# ETH_IFC.net
KiCad netlist of a schematic drawn in Altium Designer
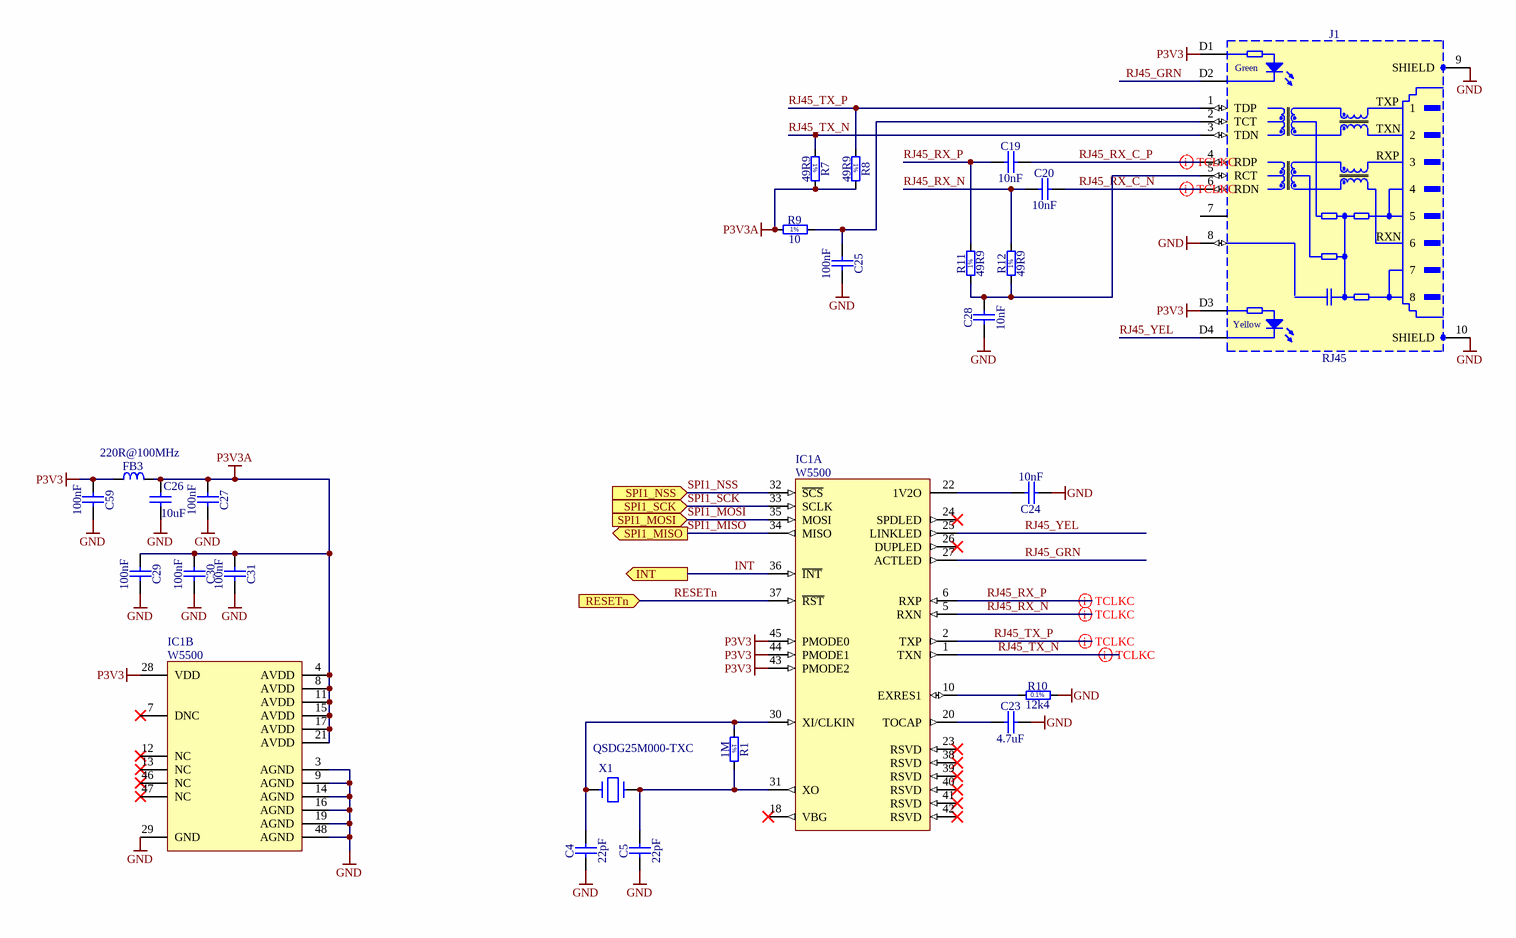
[diagram p0: ETH_IFC.SchDoc]

(export (version "E")
  (design (tool "Eeschema 10.0.6"))
  (components
    (comp (ref "C4")
      (value "22pF")
      (footprint "CAPC1005X55N")
      (description "Non-polarised capacitor")
      (fields
        (field (name "PART NUMBER") "CC0402_22PF_50V_5%_NP0")
        (field (name "VOLTAGE") "50V")
        (field (name "AUTHOR") "CERN DEM JLC")
      )
      (libsource (lib "Capacitors") (part "Capacitor - non polarized"))
    )
    (comp (ref "C5")
      (value "22pF")
      (footprint "CAPC1005X55N")
      (description "Non-polarised capacitor")
      (fields
        (field (name "PART NUMBER") "CC0402_22PF_50V_5%_NP0")
        (field (name "VOLTAGE") "50V")
        (field (name "AUTHOR") "CERN DEM JLC")
      )
      (libsource (lib "Capacitors") (part "Capacitor - non polarized"))
    )
    (comp (ref "C19")
      (value "10nF")
      (footprint "CAPC1608X87N")
      (description "Non-polarised capacitor")
      (fields
        (field (name "PART NUMBER") "CC0603_10NF_50V_5%_C0G")
        (field (name "VOLTAGE") "50V")
        (field (name "AUTHOR") "CERN DEM JLC")
      )
      (libsource (lib "Capacitors") (part "Capacitor - non polarized"))
    )
    (comp (ref "C20")
      (value "10nF")
      (footprint "CAPC1608X87N")
      (description "Non-polarised capacitor")
      (fields
        (field (name "PART NUMBER") "CC0603_10NF_50V_5%_C0G")
        (field (name "VOLTAGE") "50V")
        (field (name "AUTHOR") "CERN DEM JLC")
      )
      (libsource (lib "Capacitors") (part "Capacitor - non polarized"))
    )
    (comp (ref "C23")
      (value "4.7uF")
      (footprint "CAPC1709X95N")
      (description "Non-polarised capacitor")
      (fields
        (field (name "PART NUMBER") "CC0603_4.7UF_16V_10%_X5R")
        (field (name "VOLTAGE") "16V")
        (field (name "AUTHOR") "CERN DEM JLC")
      )
      (libsource (lib "Capacitors") (part "Capacitor - non polarized"))
    )
    (comp (ref "C24")
      (value "10nF")
      (footprint "CAPC1608X87N")
      (description "Non-polarised capacitor")
      (fields
        (field (name "PART NUMBER") "CC0603_10NF_50V_5%_C0G")
        (field (name "VOLTAGE") "50V")
        (field (name "AUTHOR") "CERN DEM JLC")
      )
      (libsource (lib "Capacitors") (part "Capacitor - non polarized"))
    )
    (comp (ref "C25")
      (value "100nF")
      (footprint "CAPC1005X55N")
      (description "Non-polarised capacitor")
      (fields
        (field (name "PART NUMBER") "CC0402_100NF_16V_10%_X7R")
        (field (name "VOLTAGE") "16V")
        (field (name "AUTHOR") "CERN DEM JLC")
      )
      (libsource (lib "Capacitors") (part "Capacitor - non polarized"))
    )
    (comp (ref "C26")
      (value "10uF")
      (footprint "CAPC2012X135N")
      (description "Non-polarised capacitor")
      (fields
        (field (name "PART NUMBER") "CC0805_10UF_10V_10%_X7R")
        (field (name "VOLTAGE") "10V")
        (field (name "AUTHOR") "CERN DEM JLC")
      )
      (libsource (lib "Capacitors") (part "Capacitor - non polarized"))
    )
    (comp (ref "C27")
      (value "100nF")
      (footprint "CAPC1005X55N")
      (description "Non-polarised capacitor")
      (fields
        (field (name "PART NUMBER") "CC0402_100NF_16V_10%_X7R")
        (field (name "VOLTAGE") "16V")
        (field (name "AUTHOR") "CERN DEM JLC")
      )
      (libsource (lib "Capacitors") (part "Capacitor - non polarized"))
    )
    (comp (ref "C28")
      (value "10nF")
      (footprint "CAPC1608X87N")
      (description "Non-polarised capacitor")
      (fields
        (field (name "PART NUMBER") "CC0603_10NF_50V_5%_C0G")
        (field (name "VOLTAGE") "50V")
        (field (name "AUTHOR") "CERN DEM JLC")
      )
      (libsource (lib "Capacitors") (part "Capacitor - non polarized"))
    )
    (comp (ref "C29")
      (value "100nF")
      (footprint "CAPC1005X55N")
      (description "Non-polarised capacitor")
      (fields
        (field (name "PART NUMBER") "CC0402_100NF_16V_10%_X7R")
        (field (name "VOLTAGE") "16V")
        (field (name "AUTHOR") "CERN DEM JLC")
      )
      (libsource (lib "Capacitors") (part "Capacitor - non polarized"))
    )
    (comp (ref "C30")
      (value "100nF")
      (footprint "CAPC1005X55N")
      (description "Non-polarised capacitor")
      (fields
        (field (name "PART NUMBER") "CC0402_100NF_16V_10%_X7R")
        (field (name "VOLTAGE") "16V")
        (field (name "AUTHOR") "CERN DEM JLC")
      )
      (libsource (lib "Capacitors") (part "Capacitor - non polarized"))
    )
    (comp (ref "C31")
      (value "100nF")
      (footprint "CAPC1005X55N")
      (description "Non-polarised capacitor")
      (fields
        (field (name "PART NUMBER") "CC0402_100NF_16V_10%_X7R")
        (field (name "VOLTAGE") "16V")
        (field (name "AUTHOR") "CERN DEM JLC")
      )
      (libsource (lib "Capacitors") (part "Capacitor - non polarized"))
    )
    (comp (ref "C59")
      (value "100nF")
      (footprint "CAPC1005X55N")
      (description "Non-polarised capacitor")
      (fields
        (field (name "PART NUMBER") "CC0402_100NF_16V_10%_X7R")
        (field (name "VOLTAGE") "16V")
        (field (name "AUTHOR") "CERN DEM JLC")
      )
      (libsource (lib "Capacitors") (part "Capacitor - non polarized"))
    )
    (comp (ref "FB3")
      (value "220R@100MHz")
      (footprint "INDC2012X105N")
      (description "Inductor")
      (fields
        (field (name "PART NUMBER") "IND0805_MURATA_BLM21PG221SN1D")
        (field (name "POWER") "2A")
        (field (name "AUTHOR") "CERN DEM JLC")
      )
      (libsource (lib "Inductors & Transformers") (part "Inductor"))
    )
    (comp (ref "IC1")
      (value "W5500")
      (footprint "QFP50P900X900X160-48N")
      (description "iEthernet W5500 TCP/IP Performance and High Speed SPI Ethernet Controller")
      (fields (field (name "MANUFACTURER") "WIZNET") (field (name "AUTHOR") "CERN DEM MR"))
      (libsource (lib "ICs And Semiconductors") (part "W5500"))
    )
    (comp (ref "J1")
      (value "RJ45")
      (footprint "TYCO_5-6605308-1")
      (fields
        (field (name "PART NUMBER") "TYCO_5-6605308-1")
        (field (name "MANUFACTURER") "TYCO ELECTRONICS")
        (field (name "MANUFACTURER PART NUMBER") "5-6605308-1")
        (field (name "AUTHOR") "CERN DEM JLC")
      )
      (libsource (lib "Connectors") (part "TYCO_5-6605308-1"))
    )
    (comp (ref "R1")
      (value "1M")
      (footprint "RESC1005X40N")
      (description "Resistor - 1%")
      (fields
        (field (name "PART NUMBER") "R0402_1M_1%_0.0625W_100PPM")
        (field (name "POWER") "0.0625W")
        (field (name "AUTHOR") "CERN DEM JLC")
      )
      (libsource (lib "Resistors") (part "Resistor - 1%"))
    )
    (comp (ref "R7")
      (value "49R9")
      (footprint "RESC1005X40N")
      (description "Resistor - 1%")
      (fields
        (field (name "PART NUMBER") "R0402_49R9_1%_0.0625W_100PPM")
        (field (name "POWER") "0.0625W")
        (field (name "AUTHOR") "CERN DEM JLC")
      )
      (libsource (lib "Resistors") (part "Resistor - 1%"))
    )
    (comp (ref "R8")
      (value "49R9")
      (footprint "RESC1005X40N")
      (description "Resistor - 1%")
      (fields
        (field (name "PART NUMBER") "R0402_49R9_1%_0.0625W_100PPM")
        (field (name "POWER") "0.0625W")
        (field (name "AUTHOR") "CERN DEM JLC")
      )
      (libsource (lib "Resistors") (part "Resistor - 1%"))
    )
    (comp (ref "R9")
      (value "10")
      (footprint "RESC1005X40N")
      (description "Resistor - 1%")
      (fields
        (field (name "PART NUMBER") "R0402_10R_1%_0.0625W_200PPM")
        (field (name "POWER") "0.0625W")
        (field (name "AUTHOR") "CERN DEM JLC")
      )
      (libsource (lib "Resistors") (part "Resistor - 1%"))
    )
    (comp (ref "R10")
      (value "12k4")
      (footprint "RESC1608X55N")
      (description "Resistor - 0.1%")
      (fields
        (field (name "PART NUMBER") "R0603_12K4_0.1%_0.063W_10PPM")
        (field (name "POWER") "0.063W")
        (field (name "AUTHOR") "CERN DEM JLC")
      )
      (libsource (lib "Resistors") (part "Resistor - 0.1%"))
    )
    (comp (ref "R11")
      (value "49R9")
      (footprint "RESC1005X40N")
      (description "Resistor - 1%")
      (fields
        (field (name "PART NUMBER") "R0402_49R9_1%_0.0625W_100PPM")
        (field (name "POWER") "0.0625W")
        (field (name "AUTHOR") "CERN DEM JLC")
      )
      (libsource (lib "Resistors") (part "Resistor - 1%"))
    )
    (comp (ref "R12")
      (value "49R9")
      (footprint "RESC1005X40N")
      (description "Resistor - 1%")
      (fields
        (field (name "PART NUMBER") "R0402_49R9_1%_0.0625W_100PPM")
        (field (name "POWER") "0.0625W")
        (field (name "AUTHOR") "CERN DEM JLC")
      )
      (libsource (lib "Resistors") (part "Resistor - 1%"))
    )
    (comp (ref "X1")
      (value "QSDG25M000-TXC")
      (footprint "XTAL_5.0*3.2")
      (description "miniature crystal oscillator (Maritex)")
      (libsource (lib "LIBRARY_SCH") (part "X_CRYSTAL_SMD_5.0*3.2"))
    )
  )
  (nets
    (net (code "1") (name "/INT") (class "Default")
      (node (ref "IC1") (pin "36") (pinfunction "~{INT}_36") (pintype "input"))
    )
    (net (code "2") (name "/RESETn") (class "Default")
      (node (ref "IC1") (pin "37") (pinfunction "~{RST}_37") (pintype "input"))
    )
    (net (code "3") (name "/RJ45_GRN") (class "Default")
      (node (ref "IC1") (pin "27") (pinfunction "ACTLED_27") (pintype "output"))
      (node (ref "J1") (pin "D2") (pinfunction "D2_D2") (pintype "passive"))
    )
    (net (code "4") (name "/RJ45_RX_C_N") (class "Default")
      (node (ref "C20") (pin "2") (pinfunction "2_2") (pintype "passive"))
      (node (ref "J1") (pin "6") (pinfunction "RDN_6") (pintype "bidirectional"))
    )
    (net (code "5") (name "/RJ45_RX_C_P") (class "Default")
      (node (ref "C19") (pin "2") (pinfunction "2_2") (pintype "passive"))
      (node (ref "J1") (pin "4") (pinfunction "RDP_4") (pintype "bidirectional"))
    )
    (net (code "6") (name "/RJ45_RX_N") (class "Default")
      (node (ref "C20") (pin "1") (pinfunction "1_1") (pintype "passive"))
      (node (ref "IC1") (pin "5") (pinfunction "RXN_5") (pintype "input"))
      (node (ref "R12") (pin "2") (pinfunction "2_2") (pintype "passive"))
    )
    (net (code "7") (name "/RJ45_RX_P") (class "Default")
      (node (ref "C19") (pin "1") (pinfunction "1_1") (pintype "passive"))
      (node (ref "IC1") (pin "6") (pinfunction "RXP_6") (pintype "input"))
      (node (ref "R11") (pin "2") (pinfunction "2_2") (pintype "passive"))
    )
    (net (code "8") (name "/RJ45_TX_N") (class "Default")
      (node (ref "IC1") (pin "1") (pinfunction "TXN_1") (pintype "output"))
      (node (ref "J1") (pin "3") (pinfunction "TDN_3") (pintype "bidirectional"))
      (node (ref "R7") (pin "1") (pinfunction "1_1") (pintype "passive"))
    )
    (net (code "9") (name "/RJ45_TX_P") (class "Default")
      (node (ref "IC1") (pin "2") (pinfunction "TXP_2") (pintype "output"))
      (node (ref "J1") (pin "1") (pinfunction "TDP_1") (pintype "bidirectional"))
      (node (ref "R8") (pin "1") (pinfunction "1_1") (pintype "passive"))
    )
    (net (code "10") (name "/RJ45_YEL") (class "Default")
      (node (ref "IC1") (pin "25") (pinfunction "LINKLED_25") (pintype "output"))
      (node (ref "J1") (pin "D4") (pinfunction "D4_D4") (pintype "passive"))
    )
    (net (code "11") (name "/SPI1_MISO") (class "Default")
      (node (ref "IC1") (pin "34") (pinfunction "MISO_34") (pintype "output"))
    )
    (net (code "12") (name "/SPI1_MOSI") (class "Default")
      (node (ref "IC1") (pin "35") (pinfunction "MOSI_35") (pintype "input"))
    )
    (net (code "13") (name "/SPI1_NSS") (class "Default")
      (node (ref "IC1") (pin "32") (pinfunction "~{SCS}_32") (pintype "input"))
    )
    (net (code "14") (name "/SPI1_SCK") (class "Default")
      (node (ref "IC1") (pin "33") (pinfunction "SCLK_33") (pintype "input"))
    )
    (net (code "15") (name "GND") (class "Default")
      (node (ref "C23") (pin "2") (pinfunction "2_2") (pintype "passive"))
      (node (ref "C24") (pin "1") (pinfunction "1_1") (pintype "passive"))
      (node (ref "C25") (pin "2") (pinfunction "2_2") (pintype "passive"))
      (node (ref "C26") (pin "2") (pinfunction "2_2") (pintype "passive"))
      (node (ref "C27") (pin "2") (pinfunction "2_2") (pintype "passive"))
      (node (ref "C28") (pin "1") (pinfunction "1_1") (pintype "passive"))
      (node (ref "C29") (pin "2") (pinfunction "2_2") (pintype "passive"))
      (node (ref "C30") (pin "2") (pinfunction "2_2") (pintype "passive"))
      (node (ref "C31") (pin "2") (pinfunction "2_2") (pintype "passive"))
      (node (ref "C4") (pin "1") (pinfunction "1_1") (pintype "passive"))
      (node (ref "C5") (pin "1") (pinfunction "1_1") (pintype "passive"))
      (node (ref "C59") (pin "2") (pinfunction "2_2") (pintype "passive"))
      (node (ref "IC1") (pin "14") (pinfunction "AGND_14") (pintype "power_in"))
      (node (ref "IC1") (pin "16") (pinfunction "AGND_16") (pintype "power_in"))
      (node (ref "IC1") (pin "19") (pinfunction "AGND_19") (pintype "power_in"))
      (node (ref "IC1") (pin "29") (pinfunction "GND_29") (pintype "power_in"))
      (node (ref "IC1") (pin "3") (pinfunction "AGND_3") (pintype "power_in"))
      (node (ref "IC1") (pin "48") (pinfunction "AGND_48") (pintype "power_in"))
      (node (ref "IC1") (pin "9") (pinfunction "AGND_9") (pintype "power_in"))
      (node (ref "J1") (pin "10") (pinfunction "SHIELD_10") (pintype "power_in"))
      (node (ref "J1") (pin "8") (pinfunction "8_8") (pintype "bidirectional"))
      (node (ref "J1") (pin "9") (pinfunction "SHIELD_9") (pintype "power_in"))
      (node (ref "R10") (pin "2") (pinfunction "2_2") (pintype "passive"))
    )
    (net (code "16") (name "Net-(IC1A-1V2O)") (class "Default")
      (node (ref "C24") (pin "2") (pinfunction "2_2") (pintype "passive"))
      (node (ref "IC1") (pin "22") (pinfunction "1V2O_22") (pintype "power_in"))
    )
    (net (code "17") (name "Net-(IC1A-EXRES1)") (class "Default")
      (node (ref "IC1") (pin "10") (pinfunction "EXRES1_10") (pintype "bidirectional"))
      (node (ref "R10") (pin "1") (pinfunction "1_1") (pintype "passive"))
    )
    (net (code "18") (name "Net-(IC1A-TOCAP)") (class "Default")
      (node (ref "C23") (pin "1") (pinfunction "1_1") (pintype "passive"))
      (node (ref "IC1") (pin "20") (pinfunction "TOCAP_20") (pintype "output"))
    )
    (net (code "19") (name "Net-(IC1A-XI{slash}CLKIN)") (class "Default")
      (node (ref "C4") (pin "2") (pinfunction "2_2") (pintype "passive"))
      (node (ref "IC1") (pin "30") (pinfunction "XI/CLKIN_30") (pintype "input"))
      (node (ref "R1") (pin "1") (pinfunction "1_1") (pintype "passive"))
      (node (ref "X1") (pin "1") (pinfunction "1_1") (pintype "passive"))
    )
    (net (code "20") (name "Net-(IC1A-XO)") (class "Default")
      (node (ref "C5") (pin "2") (pinfunction "2_2") (pintype "passive"))
      (node (ref "IC1") (pin "31") (pinfunction "XO_31") (pintype "output"))
      (node (ref "R1") (pin "2") (pinfunction "2_2") (pintype "passive"))
      (node (ref "X1") (pin "2") (pinfunction "2_2") (pintype "passive"))
    )
    (net (code "21") (name "Net-(J1-RCT)") (class "Default")
      (node (ref "C28") (pin "2") (pinfunction "2_2") (pintype "passive"))
      (node (ref "J1") (pin "5") (pinfunction "RCT_5") (pintype "bidirectional"))
      (node (ref "R11") (pin "1") (pinfunction "1_1") (pintype "passive"))
      (node (ref "R12") (pin "1") (pinfunction "1_1") (pintype "passive"))
    )
    (net (code "22") (name "Net-(J1-TCT)") (class "Default")
      (node (ref "C25") (pin "1") (pinfunction "1_1") (pintype "passive"))
      (node (ref "J1") (pin "2") (pinfunction "TCT_2") (pintype "bidirectional"))
      (node (ref "R9") (pin "2") (pinfunction "2_2") (pintype "passive"))
    )
    (net (code "23") (name "P3V3") (class "Default")
      (node (ref "C59") (pin "1") (pinfunction "1_1") (pintype "passive"))
      (node (ref "FB3") (pin "1") (pinfunction "1_1") (pintype "passive"))
      (node (ref "IC1") (pin "28") (pinfunction "VDD_28") (pintype "power_in"))
      (node (ref "IC1") (pin "43") (pinfunction "PMODE2_43") (pintype "input"))
      (node (ref "IC1") (pin "44") (pinfunction "PMODE1_44") (pintype "input"))
      (node (ref "IC1") (pin "45") (pinfunction "PMODE0_45") (pintype "input"))
      (node (ref "J1") (pin "D1") (pinfunction "D1_D1") (pintype "passive"))
      (node (ref "J1") (pin "D3") (pinfunction "D3_D3") (pintype "passive"))
    )
    (net (code "24") (name "P3V3A") (class "Default")
      (node (ref "C26") (pin "1") (pinfunction "1_1") (pintype "passive"))
      (node (ref "C27") (pin "1") (pinfunction "1_1") (pintype "passive"))
      (node (ref "C29") (pin "1") (pinfunction "1_1") (pintype "passive"))
      (node (ref "C30") (pin "1") (pinfunction "1_1") (pintype "passive"))
      (node (ref "C31") (pin "1") (pinfunction "1_1") (pintype "passive"))
      (node (ref "FB3") (pin "2") (pinfunction "2_2") (pintype "passive"))
      (node (ref "IC1") (pin "11") (pinfunction "AVDD_11") (pintype "power_in"))
      (node (ref "IC1") (pin "15") (pinfunction "AVDD_15") (pintype "power_in"))
      (node (ref "IC1") (pin "17") (pinfunction "AVDD_17") (pintype "power_in"))
      (node (ref "IC1") (pin "21") (pinfunction "AVDD_21") (pintype "power_in"))
      (node (ref "IC1") (pin "4") (pinfunction "AVDD_4") (pintype "power_in"))
      (node (ref "IC1") (pin "8") (pinfunction "AVDD_8") (pintype "power_in"))
      (node (ref "R7") (pin "2") (pinfunction "2_2") (pintype "passive"))
      (node (ref "R8") (pin "2") (pinfunction "2_2") (pintype "passive"))
      (node (ref "R9") (pin "1") (pinfunction "1_1") (pintype "passive"))
    )
    (net (code "25") (name "unconnected-(IC1A-DUPLED-Pad26)") (class "Default")
      (node (ref "IC1") (pin "26") (pinfunction "DUPLED_26") (pintype "output+no_connect"))
    )
    (net (code "26") (name "unconnected-(IC1A-RSVD-Pad23)") (class "Default")
      (node (ref "IC1") (pin "23") (pinfunction "RSVD_23") (pintype "input+no_connect"))
    )
    (net (code "27") (name "unconnected-(IC1A-RSVD-Pad38)") (class "Default")
      (node (ref "IC1") (pin "38") (pinfunction "RSVD_38") (pintype "input+no_connect"))
    )
    (net (code "28") (name "unconnected-(IC1A-RSVD-Pad39)") (class "Default")
      (node (ref "IC1") (pin "39") (pinfunction "RSVD_39") (pintype "input+no_connect"))
    )
    (net (code "29") (name "unconnected-(IC1A-RSVD-Pad40)") (class "Default")
      (node (ref "IC1") (pin "40") (pinfunction "RSVD_40") (pintype "input+no_connect"))
    )
    (net (code "30") (name "unconnected-(IC1A-RSVD-Pad41)") (class "Default")
      (node (ref "IC1") (pin "41") (pinfunction "RSVD_41") (pintype "input+no_connect"))
    )
    (net (code "31") (name "unconnected-(IC1A-RSVD-Pad42)") (class "Default")
      (node (ref "IC1") (pin "42") (pinfunction "RSVD_42") (pintype "input+no_connect"))
    )
    (net (code "32") (name "unconnected-(IC1A-SPDLED-Pad24)") (class "Default")
      (node (ref "IC1") (pin "24") (pinfunction "SPDLED_24") (pintype "output+no_connect"))
    )
    (net (code "33") (name "unconnected-(IC1A-VBG-Pad18)") (class "Default")
      (node (ref "IC1") (pin "18") (pinfunction "VBG_18") (pintype "output+no_connect"))
    )
    (net (code "34") (name "unconnected-(IC1B-DNC-Pad7)") (class "Default")
      (node (ref "IC1") (pin "7") (pinfunction "DNC_7") (pintype "passive+no_connect"))
    )
    (net (code "35") (name "unconnected-(IC1B-NC-Pad12)") (class "Default")
      (node (ref "IC1") (pin "12") (pinfunction "NC_12") (pintype "passive+no_connect"))
    )
    (net (code "36") (name "unconnected-(IC1B-NC-Pad13)") (class "Default")
      (node (ref "IC1") (pin "13") (pinfunction "NC_13") (pintype "passive+no_connect"))
    )
    (net (code "37") (name "unconnected-(IC1B-NC-Pad46)") (class "Default")
      (node (ref "IC1") (pin "46") (pinfunction "NC_46") (pintype "passive+no_connect"))
    )
    (net (code "38") (name "unconnected-(IC1B-NC-Pad47)") (class "Default")
      (node (ref "IC1") (pin "47") (pinfunction "NC_47") (pintype "passive+no_connect"))
    )
    (net (code "39") (name "unconnected-(J1-Pad7)") (class "Default")
      (node (ref "J1") (pin "7") (pinfunction "7_7") (pintype "passive"))
    )
  )
)
